# SensingMethods.net
KiCad netlist of a schematic drawn in EAGLE
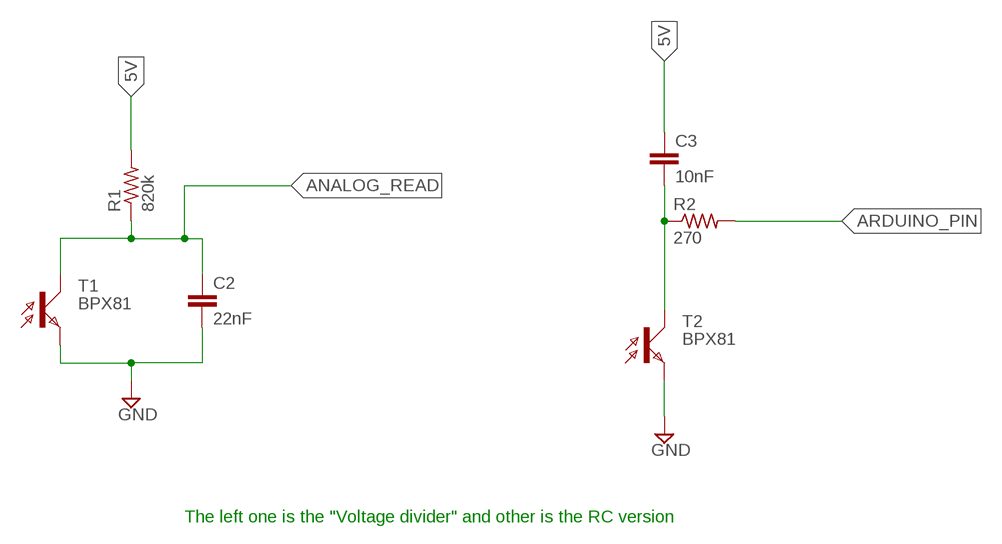
[diagram p0: schematic, sheet 1]

(export (version "E")
  (design (tool "Eeschema 10.0.6"))
  (components
    (comp (ref "C2")
      (value "22nF")
      (footprint "eagle-import:C1808")
      (libsource (lib "eagle-import") (part "C-EUC1808"))
    )
    (comp (ref "C3")
      (value "10nF")
      (footprint "eagle-import:C1808")
      (libsource (lib "eagle-import") (part "C-EUC1808"))
    )
    (comp (ref "R1")
      (value "820k")
      (footprint "eagle-import:R0805")
      (libsource (lib "eagle-import") (part "R-US_R0805"))
    )
    (comp (ref "R2")
      (value "270")
      (footprint "eagle-import:R1210")
      (libsource (lib "eagle-import") (part "R-US_R1210"))
    )
    (comp (ref "T1")
      (value "BPX81")
      (footprint "eagle-import:BPX81")
      (libsource (lib "eagle-import") (part "BPX81"))
    )
    (comp (ref "T2")
      (value "BPX81")
      (footprint "eagle-import:BPX81")
      (libsource (lib "eagle-import") (part "BPX81"))
    )
  )
  (nets
    (net (code "1") (name "5V") (class "Default")
      (node (ref "C3") (pin "1") (pinfunction "1_1") (pintype "passive"))
      (node (ref "R1") (pin "2") (pinfunction "2_2") (pintype "passive"))
    )
    (net (code "2") (name "ANALOG_READ") (class "Default")
      (node (ref "C2") (pin "1") (pinfunction "1_1") (pintype "passive"))
      (node (ref "R1") (pin "1") (pinfunction "1_1") (pintype "passive"))
      (node (ref "T1") (pin "C") (pinfunction "C_C") (pintype "passive"))
    )
    (net (code "3") (name "ARDUINO_PIN") (class "Default")
      (node (ref "R2") (pin "2") (pinfunction "2_2") (pintype "passive"))
    )
    (net (code "4") (name "GND") (class "Default")
      (node (ref "C2") (pin "2") (pinfunction "2_2") (pintype "passive"))
      (node (ref "T1") (pin "E") (pinfunction "E_E") (pintype "passive"))
      (node (ref "T2") (pin "E") (pinfunction "E_E") (pintype "passive"))
    )
    (net (code "5") (name "Net-(C3-Pad2)") (class "Default")
      (node (ref "C3") (pin "2") (pinfunction "2_2") (pintype "passive"))
      (node (ref "R2") (pin "1") (pinfunction "1_1") (pintype "passive"))
      (node (ref "T2") (pin "C") (pinfunction "C_C") (pintype "passive"))
    )
  )
)
